# design.net
KiCad netlist of a schematic drawn in Altium Designer
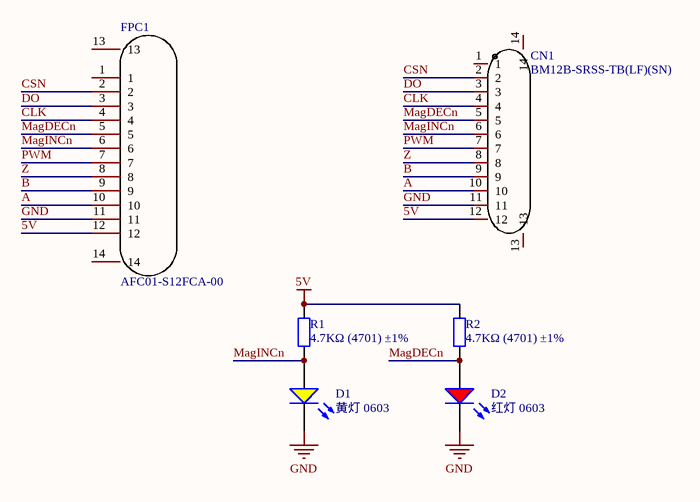
[diagram p0: 转接板.SchDoc]

(export (version "E")
  (design (tool "Eeschema 10.0.6"))
  (components
    (comp (ref "CN1")
      (value "BM12B-SRSS-TB(LF)(SN)")
      (footprint "CONN-SMD_BM12B-SRSS-TB-LF-SN")
      (fields (field (name "MANUFACTURER") "JST") (field (name "NAME") "BM12B-SRSS-TB(LF)(SN)"))
      (libsource (lib "MyLib") (part "BM12B-SRSS-TB(LF)(SN)"))
    )
    (comp (ref "D1")
      (value "黄灯 0603")
      (footprint "0603_LED_S1")
      (description "发光二极管")
      (libsource (lib "Miscellaneous Devices LC") (part "0603 黄灯"))
    )
    (comp (ref "D2")
      (value "红灯 0603")
      (footprint "0603_LED_S1")
      (description "发光二极管")
      (libsource (lib "Miscellaneous Devices LC") (part "0603 红灯"))
    )
    (comp (ref "FPC1")
      (value "AFC01-S12FCA-00")
      (footprint "FPC-SMD_AFC01-S12FCA-00")
      (description "间距:0.5mm;触点数量:12P;锁定特性:翻盖式;触点类型:下接;安装类型:卧贴;")
      (fields (field (name "MANUFACTURER") "JS(钜硕电子)") (field (name "NAME") "AFC01-S12FCA-00"))
      (libsource (lib "MyLib") (part "AFC01-S12FCA-00"))
    )
    (comp (ref "R1")
      (value "4.7KΩ (4701) ±1%")
      (footprint "0603_R")
      (description "贴片电阻")
      (libsource (lib "Miscellaneous Devices LC") (part "0603 4.7KΩ (4701) 1%"))
    )
    (comp (ref "R2")
      (value "4.7KΩ (4701) ±1%")
      (footprint "0603_R")
      (description "贴片电阻")
      (libsource (lib "Miscellaneous Devices LC") (part "0603 4.7KΩ (4701) 1%"))
    )
  )
  (nets
    (net (code "1") (name "/A") (class "Default")
      (node (ref "CN1") (pin "10") (pinfunction "10_10") (pintype "passive"))
      (node (ref "FPC1") (pin "10") (pinfunction "10_10") (pintype "passive"))
    )
    (net (code "2") (name "/B") (class "Default")
      (node (ref "CN1") (pin "9") (pinfunction "9_9") (pintype "passive"))
      (node (ref "FPC1") (pin "9") (pinfunction "9_9") (pintype "passive"))
    )
    (net (code "3") (name "/CLK") (class "Default")
      (node (ref "CN1") (pin "4") (pinfunction "4_4") (pintype "passive"))
      (node (ref "FPC1") (pin "4") (pinfunction "4_4") (pintype "passive"))
    )
    (net (code "4") (name "/CSN") (class "Default")
      (node (ref "CN1") (pin "2") (pinfunction "2_2") (pintype "passive"))
      (node (ref "FPC1") (pin "2") (pinfunction "2_2") (pintype "passive"))
    )
    (net (code "5") (name "/DO") (class "Default")
      (node (ref "CN1") (pin "3") (pinfunction "3_3") (pintype "passive"))
      (node (ref "FPC1") (pin "3") (pinfunction "3_3") (pintype "passive"))
    )
    (net (code "6") (name "/MagDECn") (class "Default")
      (node (ref "CN1") (pin "5") (pinfunction "5_5") (pintype "passive"))
      (node (ref "D2") (pin "A") (pinfunction "A_A") (pintype "passive"))
      (node (ref "FPC1") (pin "5") (pinfunction "5_5") (pintype "passive"))
      (node (ref "R2") (pin "1") (pinfunction "1_1") (pintype "passive"))
    )
    (net (code "7") (name "/MagINCn") (class "Default")
      (node (ref "CN1") (pin "6") (pinfunction "6_6") (pintype "passive"))
      (node (ref "D1") (pin "A") (pinfunction "A_A") (pintype "passive"))
      (node (ref "FPC1") (pin "6") (pinfunction "6_6") (pintype "passive"))
      (node (ref "R1") (pin "1") (pinfunction "1_1") (pintype "passive"))
    )
    (net (code "8") (name "/PWM") (class "Default")
      (node (ref "CN1") (pin "7") (pinfunction "7_7") (pintype "passive"))
      (node (ref "FPC1") (pin "7") (pinfunction "7_7") (pintype "passive"))
    )
    (net (code "9") (name "/Z") (class "Default")
      (node (ref "CN1") (pin "8") (pinfunction "8_8") (pintype "passive"))
      (node (ref "FPC1") (pin "8") (pinfunction "8_8") (pintype "passive"))
    )
    (net (code "10") (name "5V") (class "Default")
      (node (ref "CN1") (pin "12") (pinfunction "12_12") (pintype "passive"))
      (node (ref "FPC1") (pin "12") (pinfunction "12_12") (pintype "passive"))
      (node (ref "R1") (pin "2") (pinfunction "2_2") (pintype "passive"))
      (node (ref "R2") (pin "2") (pinfunction "2_2") (pintype "passive"))
    )
    (net (code "11") (name "GND") (class "Default")
      (node (ref "CN1") (pin "11") (pinfunction "11_11") (pintype "passive"))
      (node (ref "D1") (pin "K") (pinfunction "K_K") (pintype "passive"))
      (node (ref "D2") (pin "K") (pinfunction "K_K") (pintype "passive"))
      (node (ref "FPC1") (pin "11") (pinfunction "11_11") (pintype "passive"))
    )
    (net (code "12") (name "unconnected-(CN1-Pad1)") (class "Default")
      (node (ref "CN1") (pin "1") (pinfunction "1_1") (pintype "passive"))
    )
    (net (code "13") (name "unconnected-(CN1-Pad13)") (class "Default")
      (node (ref "CN1") (pin "13") (pinfunction "13_13") (pintype "passive"))
    )
    (net (code "14") (name "unconnected-(CN1-Pad14)") (class "Default")
      (node (ref "CN1") (pin "14") (pinfunction "14_14") (pintype "passive"))
    )
    (net (code "15") (name "unconnected-(FPC1-Pad1)") (class "Default")
      (node (ref "FPC1") (pin "1") (pinfunction "1_1") (pintype "passive"))
    )
    (net (code "16") (name "unconnected-(FPC1-Pad13)") (class "Default")
      (node (ref "FPC1") (pin "13") (pinfunction "13_13") (pintype "passive"))
    )
    (net (code "17") (name "unconnected-(FPC1-Pad14)") (class "Default")
      (node (ref "FPC1") (pin "14") (pinfunction "14_14") (pintype "passive"))
    )
  )
)
